# BBB.net
KiCad netlist of a schematic drawn in Altium Designer
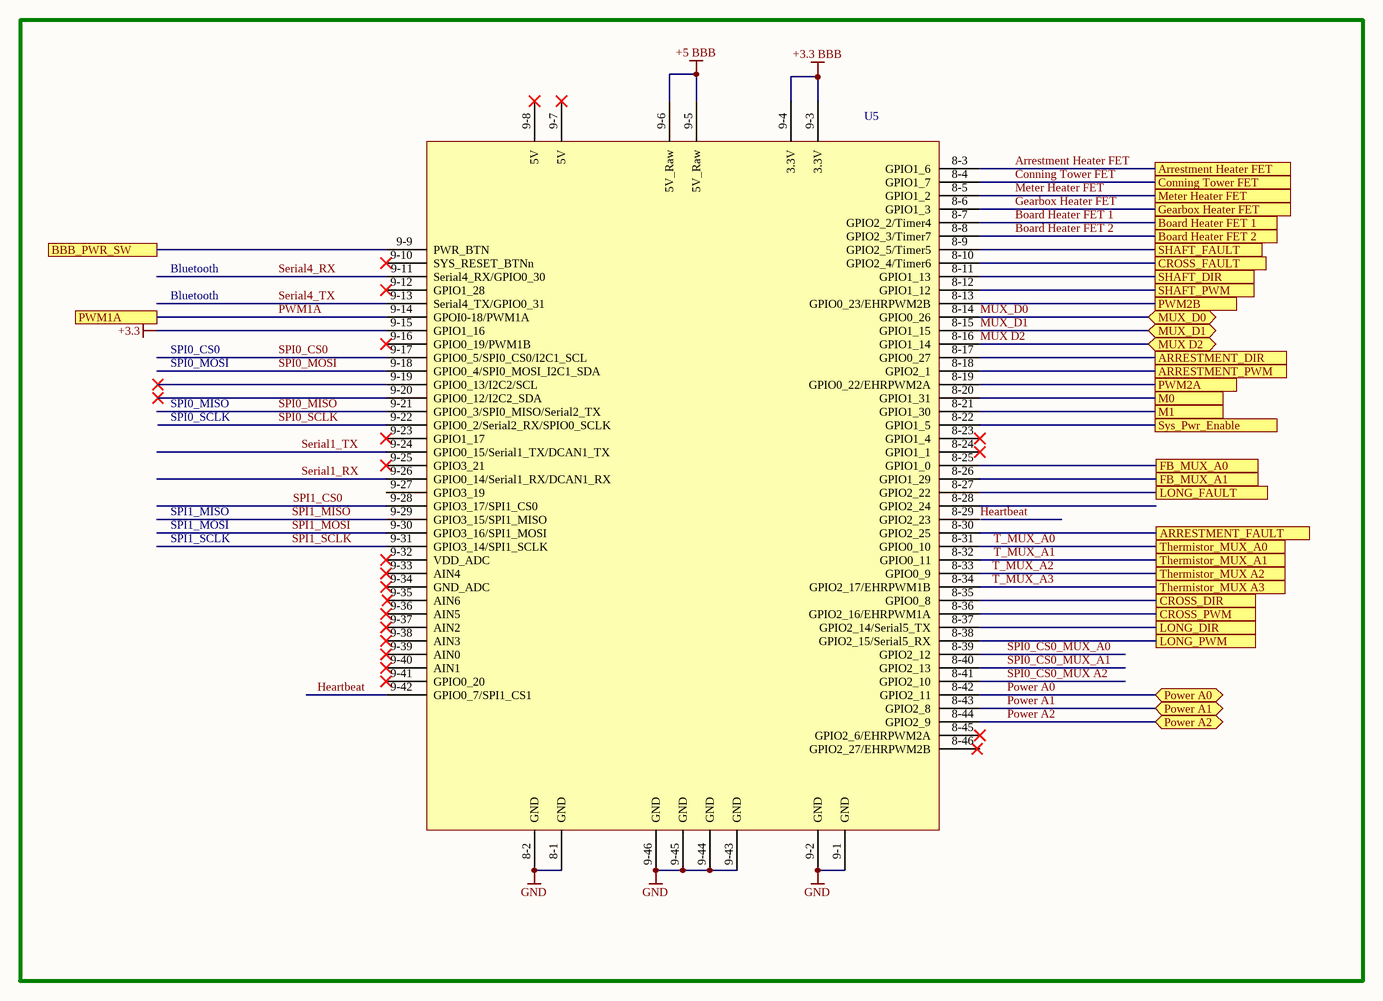
[diagram p0: BBB.SchDoc]

(export (version "E")
  (design (tool "Eeschema 10.0.6"))
  (components
    (comp (ref "U5")
      (value "BBB Header x 2")
      (footprint "Beaglebone Black Thru")
      (description "Beaglebone Black Header")
      (fields
        (field (name "MANUFACTURER") "Samtec Inc.")
        (field (name "MANUFACTURER PART NUMBER") "SSW-123-03-G-D")
      )
      (libsource (lib "ZLS_Schematic_lib") (part "Beaglebone_Black"))
    )
  )
  (nets
    (net (code "1") (name "+3.3") (class "Default")
      (node (ref "U5") (pin "9-15") (pinfunction "GPIO1_16_9-15") (pintype "passive"))
    )
    (net (code "2") (name "+3.3 BBB") (class "Default")
      (node (ref "U5") (pin "9-3") (pinfunction "3.3V_9-3") (pintype "passive"))
      (node (ref "U5") (pin "9-4") (pinfunction "3.3V_9-4") (pintype "passive"))
    )
    (net (code "3") (name "+5 BBB") (class "Default")
      (node (ref "U5") (pin "9-5") (pinfunction "5V_Raw_9-5") (pintype "passive"))
      (node (ref "U5") (pin "9-6") (pinfunction "5V_Raw_9-6") (pintype "passive"))
    )
    (net (code "4") (name "/ARRESTMENT_DIR") (class "Default")
      (node (ref "U5") (pin "8-17") (pinfunction "GPIO0_27_8-17") (pintype "passive"))
    )
    (net (code "5") (name "/ARRESTMENT_FAULT") (class "Default")
      (node (ref "U5") (pin "8-30") (pinfunction "GPIO2_25_8-30") (pintype "passive"))
    )
    (net (code "6") (name "/ARRESTMENT_PWM") (class "Default")
      (node (ref "U5") (pin "8-18") (pinfunction "GPIO2_1_8-18") (pintype "passive"))
    )
    (net (code "7") (name "/Arrestment Heater FET") (class "Default")
      (node (ref "U5") (pin "8-3") (pinfunction "GPIO1_6_8-3") (pintype "passive"))
    )
    (net (code "8") (name "/BBB_PWR_SW") (class "Default")
      (node (ref "U5") (pin "9-9") (pinfunction "PWR_BTN_9-9") (pintype "passive"))
    )
    (net (code "9") (name "/Board Heater FET 1") (class "Default")
      (node (ref "U5") (pin "8-7") (pinfunction "GPIO2_2/Timer4_8-7") (pintype "passive"))
    )
    (net (code "10") (name "/Board Heater FET 2") (class "Default")
      (node (ref "U5") (pin "8-8") (pinfunction "GPIO2_3/Timer7_8-8") (pintype "passive"))
    )
    (net (code "11") (name "/CROSS_DIR") (class "Default")
      (node (ref "U5") (pin "8-35") (pinfunction "GPIO0_8_8-35") (pintype "passive"))
    )
    (net (code "12") (name "/CROSS_FAULT") (class "Default")
      (node (ref "U5") (pin "8-10") (pinfunction "GPIO2_4/Timer6_8-10") (pintype "passive"))
    )
    (net (code "13") (name "/CROSS_PWM") (class "Default")
      (node (ref "U5") (pin "8-36") (pinfunction "GPIO2_16/EHRPWM1A_8-36") (pintype "passive"))
    )
    (net (code "14") (name "/Conning Tower FET") (class "Default")
      (node (ref "U5") (pin "8-4") (pinfunction "GPIO1_7_8-4") (pintype "passive"))
    )
    (net (code "15") (name "/FB_MUX_A0") (class "Default")
      (node (ref "U5") (pin "8-25") (pinfunction "GPIO1_0_8-25") (pintype "passive"))
    )
    (net (code "16") (name "/FB_MUX_A1") (class "Default")
      (node (ref "U5") (pin "8-26") (pinfunction "GPIO1_29_8-26") (pintype "passive"))
    )
    (net (code "17") (name "/Gearbox Heater FET") (class "Default")
      (node (ref "U5") (pin "8-6") (pinfunction "GPIO1_3_8-6") (pintype "passive"))
    )
    (net (code "18") (name "/Heartbeat") (class "Default")
      (node (ref "U5") (pin "8-29") (pinfunction "GPIO2_23_8-29") (pintype "passive"))
      (node (ref "U5") (pin "9-42") (pinfunction "GPIO0_7/SPI1_CS1_9-42") (pintype "passive"))
    )
    (net (code "19") (name "/LONG_DIR") (class "Default")
      (node (ref "U5") (pin "8-37") (pinfunction "GPIO2_14/Serial5_TX_8-37") (pintype "passive"))
    )
    (net (code "20") (name "/LONG_FAULT") (class "Default")
      (node (ref "U5") (pin "8-27") (pinfunction "GPIO2_22_8-27") (pintype "passive"))
    )
    (net (code "21") (name "/LONG_PWM") (class "Default")
      (node (ref "U5") (pin "8-38") (pinfunction "GPIO2_15/Serial5_RX_8-38") (pintype "passive"))
    )
    (net (code "22") (name "/M0") (class "Default")
      (node (ref "U5") (pin "8-20") (pinfunction "GPIO1_31_8-20") (pintype "passive"))
    )
    (net (code "23") (name "/M1") (class "Default")
      (node (ref "U5") (pin "8-21") (pinfunction "GPIO1_30_8-21") (pintype "passive"))
    )
    (net (code "24") (name "/MUX D2") (class "Default")
      (node (ref "U5") (pin "8-16") (pinfunction "GPIO1_14_8-16") (pintype "passive"))
    )
    (net (code "25") (name "/MUX_D0") (class "Default")
      (node (ref "U5") (pin "8-14") (pinfunction "GPIO0_26_8-14") (pintype "passive"))
    )
    (net (code "26") (name "/MUX_D1") (class "Default")
      (node (ref "U5") (pin "8-15") (pinfunction "GPIO1_15_8-15") (pintype "passive"))
    )
    (net (code "27") (name "/Meter Heater FET") (class "Default")
      (node (ref "U5") (pin "8-5") (pinfunction "GPIO1_2_8-5") (pintype "passive"))
    )
    (net (code "28") (name "/PWM1A") (class "Default")
      (node (ref "U5") (pin "9-14") (pinfunction "GPOI0-18/PWM1A_9-14") (pintype "passive"))
    )
    (net (code "29") (name "/PWM2A") (class "Default")
      (node (ref "U5") (pin "8-19") (pinfunction "GPIO0_22/EHRPWM2A_8-19") (pintype "passive"))
    )
    (net (code "30") (name "/PWM2B") (class "Default")
      (node (ref "U5") (pin "8-13") (pinfunction "GPIO0_23/EHRPWM2B_8-13") (pintype "passive"))
    )
    (net (code "31") (name "/Power A0") (class "Default")
      (node (ref "U5") (pin "8-42") (pinfunction "GPIO2_11_8-42") (pintype "passive"))
    )
    (net (code "32") (name "/Power A1") (class "Default")
      (node (ref "U5") (pin "8-43") (pinfunction "GPIO2_8_8-43") (pintype "passive"))
    )
    (net (code "33") (name "/Power A2") (class "Default")
      (node (ref "U5") (pin "8-44") (pinfunction "GPIO2_9_8-44") (pintype "passive"))
    )
    (net (code "34") (name "/SHAFT_DIR") (class "Default")
      (node (ref "U5") (pin "8-11") (pinfunction "GPIO1_13_8-11") (pintype "passive"))
    )
    (net (code "35") (name "/SHAFT_FAULT") (class "Default")
      (node (ref "U5") (pin "8-9") (pinfunction "GPIO2_5/Timer5_8-9") (pintype "passive"))
    )
    (net (code "36") (name "/SHAFT_PWM") (class "Default")
      (node (ref "U5") (pin "8-12") (pinfunction "GPIO1_12_8-12") (pintype "passive"))
    )
    (net (code "37") (name "/SPI0_CS0") (class "Default")
      (node (ref "U5") (pin "9-17") (pinfunction "GPIO0_5/SPI0_CS0/I2C1_SCL_9-17") (pintype "passive"))
    )
    (net (code "38") (name "/SPI0_CS0_MUX A2") (class "Default")
      (node (ref "U5") (pin "8-41") (pinfunction "GPIO2_10_8-41") (pintype "passive"))
    )
    (net (code "39") (name "/SPI0_CS0_MUX_A0") (class "Default")
      (node (ref "U5") (pin "8-39") (pinfunction "GPIO2_12_8-39") (pintype "passive"))
    )
    (net (code "40") (name "/SPI0_CS0_MUX_A1") (class "Default")
      (node (ref "U5") (pin "8-40") (pinfunction "GPIO2_13_8-40") (pintype "passive"))
    )
    (net (code "41") (name "/SPI0_MISO") (class "Default")
      (node (ref "U5") (pin "9-21") (pinfunction "GPIO0_3/SPI0_MISO/Serial2_TX_9-21") (pintype "passive"))
    )
    (net (code "42") (name "/SPI0_MOSI") (class "Default")
      (node (ref "U5") (pin "9-18") (pinfunction "GPIO0_4/SPI0_MOSI_I2C1_SDA_9-18") (pintype "passive"))
    )
    (net (code "43") (name "/SPI0_SCLK") (class "Default")
      (node (ref "U5") (pin "9-22") (pinfunction "GPIO0_2/Serial2_RX/SPIO0_SCLK_9-22") (pintype "passive"))
    )
    (net (code "44") (name "/SPI1_CS0") (class "Default")
      (node (ref "U5") (pin "9-28") (pinfunction "GPIO3_17/SPI1_CS0_9-28") (pintype "passive"))
    )
    (net (code "45") (name "/SPI1_MISO") (class "Default")
      (node (ref "U5") (pin "9-29") (pinfunction "GPIO3_15/SPI1_MISO_9-29") (pintype "passive"))
    )
    (net (code "46") (name "/SPI1_MOSI") (class "Default")
      (node (ref "U5") (pin "9-30") (pinfunction "GPIO3_16/SPI1_MOSI_9-30") (pintype "passive"))
    )
    (net (code "47") (name "/SPI1_SCLK") (class "Default")
      (node (ref "U5") (pin "9-31") (pinfunction "GPIO3_14/SPI1_SCLK_9-31") (pintype "passive"))
    )
    (net (code "48") (name "/Serial1_RX") (class "Default")
      (node (ref "U5") (pin "9-26") (pinfunction "GPIO0_14/Serial1_RX/DCAN1_RX_9-26") (pintype "passive"))
    )
    (net (code "49") (name "/Serial1_TX") (class "Default")
      (node (ref "U5") (pin "9-24") (pinfunction "GPIO0_15/Serial1_TX/DCAN1_TX_9-24") (pintype "passive"))
    )
    (net (code "50") (name "/Serial4_RX") (class "Default")
      (node (ref "U5") (pin "9-11") (pinfunction "Serial4_RX/GPIO0_30_9-11") (pintype "passive"))
    )
    (net (code "51") (name "/Serial4_TX") (class "Default")
      (node (ref "U5") (pin "9-13") (pinfunction "Serial4_TX/GPIO0_31_9-13") (pintype "passive"))
    )
    (net (code "52") (name "/Sys_Pwr_Enable") (class "Default")
      (node (ref "U5") (pin "8-22") (pinfunction "GPIO1_5_8-22") (pintype "passive"))
    )
    (net (code "53") (name "/T_MUX_A0") (class "Default")
      (node (ref "U5") (pin "8-31") (pinfunction "GPIO0_10_8-31") (pintype "passive"))
    )
    (net (code "54") (name "/T_MUX_A1") (class "Default")
      (node (ref "U5") (pin "8-32") (pinfunction "GPIO0_11_8-32") (pintype "passive"))
    )
    (net (code "55") (name "/T_MUX_A2") (class "Default")
      (node (ref "U5") (pin "8-33") (pinfunction "GPIO0_9_8-33") (pintype "passive"))
    )
    (net (code "56") (name "/T_MUX_A3") (class "Default")
      (node (ref "U5") (pin "8-34") (pinfunction "GPIO2_17/EHRPWM1B_8-34") (pintype "passive"))
    )
    (net (code "57") (name "GND") (class "Default")
      (node (ref "U5") (pin "8-1") (pinfunction "GND_8-1") (pintype "passive"))
      (node (ref "U5") (pin "8-2") (pinfunction "GND_8-2") (pintype "passive"))
      (node (ref "U5") (pin "9-1") (pinfunction "GND_9-1") (pintype "passive"))
      (node (ref "U5") (pin "9-2") (pinfunction "GND_9-2") (pintype "passive"))
      (node (ref "U5") (pin "9-43") (pinfunction "GND_9-43") (pintype "passive"))
      (node (ref "U5") (pin "9-44") (pinfunction "GND_9-44") (pintype "passive"))
      (node (ref "U5") (pin "9-45") (pinfunction "GND_9-45") (pintype "passive"))
      (node (ref "U5") (pin "9-46") (pinfunction "GND_9-46") (pintype "passive"))
    )
    (net (code "58") (name "unconnected-(U5-5V-Pad9-7)") (class "Default")
      (node (ref "U5") (pin "9-7") (pinfunction "5V_9-7") (pintype "passive+no_connect"))
    )
    (net (code "59") (name "unconnected-(U5-5V-Pad9-8)") (class "Default")
      (node (ref "U5") (pin "9-8") (pinfunction "5V_9-8") (pintype "passive+no_connect"))
    )
    (net (code "60") (name "unconnected-(U5-AIN0-Pad9-39)") (class "Default")
      (node (ref "U5") (pin "9-39") (pinfunction "AIN0_9-39") (pintype "passive+no_connect"))
    )
    (net (code "61") (name "unconnected-(U5-AIN1-Pad9-40)") (class "Default")
      (node (ref "U5") (pin "9-40") (pinfunction "AIN1_9-40") (pintype "passive+no_connect"))
    )
    (net (code "62") (name "unconnected-(U5-AIN2-Pad9-37)") (class "Default")
      (node (ref "U5") (pin "9-37") (pinfunction "AIN2_9-37") (pintype "passive+no_connect"))
    )
    (net (code "63") (name "unconnected-(U5-AIN3-Pad9-38)") (class "Default")
      (node (ref "U5") (pin "9-38") (pinfunction "AIN3_9-38") (pintype "passive+no_connect"))
    )
    (net (code "64") (name "unconnected-(U5-AIN4-Pad9-33)") (class "Default")
      (node (ref "U5") (pin "9-33") (pinfunction "AIN4_9-33") (pintype "passive+no_connect"))
    )
    (net (code "65") (name "unconnected-(U5-AIN5-Pad9-36)") (class "Default")
      (node (ref "U5") (pin "9-36") (pinfunction "AIN5_9-36") (pintype "passive+no_connect"))
    )
    (net (code "66") (name "unconnected-(U5-AIN6-Pad9-35)") (class "Default")
      (node (ref "U5") (pin "9-35") (pinfunction "AIN6_9-35") (pintype "passive"))
    )
    (net (code "67") (name "unconnected-(U5-GND_ADC-Pad9-34)") (class "Default")
      (node (ref "U5") (pin "9-34") (pinfunction "GND_ADC_9-34") (pintype "passive+no_connect"))
    )
    (net (code "68") (name "unconnected-(U5-GPIO0_12{slash}I2C2_SDA-Pad9-20)") (class "Default")
      (node (ref "U5") (pin "9-20") (pinfunction "GPIO0_12/I2C2_SDA_9-20") (pintype "passive+no_connect"))
    )
    (net (code "69") (name "unconnected-(U5-GPIO0_13{slash}I2C2{slash}SCL-Pad9-19)") (class "Default")
      (node (ref "U5") (pin "9-19") (pinfunction "GPIO0_13/I2C2/SCL_9-19") (pintype "passive+no_connect"))
    )
    (net (code "70") (name "unconnected-(U5-GPIO0_19{slash}PWM1B-Pad9-16)") (class "Default")
      (node (ref "U5") (pin "9-16") (pinfunction "GPIO0_19/PWM1B_9-16") (pintype "passive+no_connect"))
    )
    (net (code "71") (name "unconnected-(U5-GPIO0_20-Pad9-41)") (class "Default")
      (node (ref "U5") (pin "9-41") (pinfunction "GPIO0_20_9-41") (pintype "passive+no_connect"))
    )
    (net (code "72") (name "unconnected-(U5-GPIO1_1-Pad8-24)") (class "Default")
      (node (ref "U5") (pin "8-24") (pinfunction "GPIO1_1_8-24") (pintype "passive+no_connect"))
    )
    (net (code "73") (name "unconnected-(U5-GPIO1_4-Pad8-23)") (class "Default")
      (node (ref "U5") (pin "8-23") (pinfunction "GPIO1_4_8-23") (pintype "passive+no_connect"))
    )
    (net (code "74") (name "unconnected-(U5-GPIO1_17-Pad9-23)") (class "Default")
      (node (ref "U5") (pin "9-23") (pinfunction "GPIO1_17_9-23") (pintype "passive+no_connect"))
    )
    (net (code "75") (name "unconnected-(U5-GPIO1_28-Pad9-12)") (class "Default")
      (node (ref "U5") (pin "9-12") (pinfunction "GPIO1_28_9-12") (pintype "passive+no_connect"))
    )
    (net (code "76") (name "unconnected-(U5-GPIO2_6{slash}EHRPWM2A-Pad8-45)") (class "Default")
      (node (ref "U5") (pin "8-45") (pinfunction "GPIO2_6/EHRPWM2A_8-45") (pintype "passive+no_connect"))
    )
    (net (code "77") (name "unconnected-(U5-GPIO2_24-Pad8-28)") (class "Default")
      (node (ref "U5") (pin "8-28") (pinfunction "GPIO2_24_8-28") (pintype "passive"))
    )
    (net (code "78") (name "unconnected-(U5-GPIO2_27{slash}EHRPWM2B-Pad8-46)") (class "Default")
      (node (ref "U5") (pin "8-46") (pinfunction "GPIO2_27/EHRPWM2B_8-46") (pintype "passive"))
    )
    (net (code "79") (name "unconnected-(U5-GPIO3_19-Pad9-27)") (class "Default")
      (node (ref "U5") (pin "9-27") (pinfunction "GPIO3_19_9-27") (pintype "passive"))
    )
    (net (code "80") (name "unconnected-(U5-GPIO3_21-Pad9-25)") (class "Default")
      (node (ref "U5") (pin "9-25") (pinfunction "GPIO3_21_9-25") (pintype "passive+no_connect"))
    )
    (net (code "81") (name "unconnected-(U5-SYS_RESET_BTNn-Pad9-10)") (class "Default")
      (node (ref "U5") (pin "9-10") (pinfunction "SYS_RESET_BTNn_9-10") (pintype "passive+no_connect"))
    )
    (net (code "82") (name "unconnected-(U5-VDD_ADC-Pad9-32)") (class "Default")
      (node (ref "U5") (pin "9-32") (pinfunction "VDD_ADC_9-32") (pintype "passive+no_connect"))
    )
  )
)
